# display.net
KiCad netlist of a schematic drawn in Altium Designer
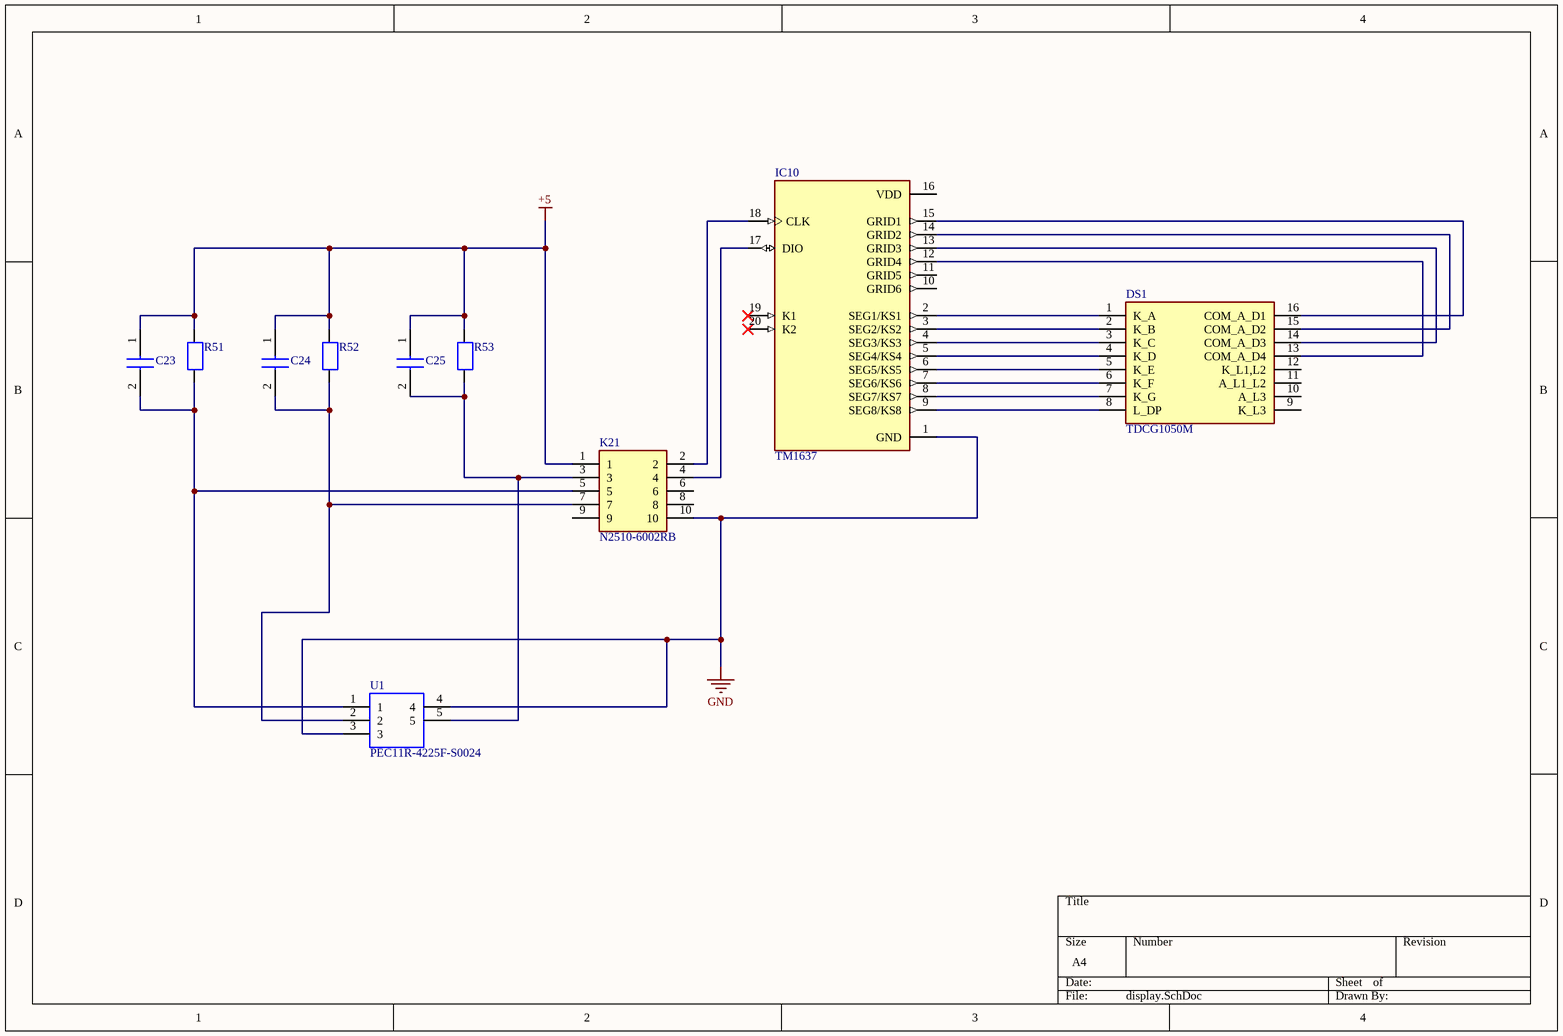
[diagram p0: display.SchDoc]

(export (version "E")
  (design (tool "Eeschema 10.0.6"))
  (components
    (comp (ref "C23")
      (value "08055A130JAT2A")
      (footprint "SamacSys:CAPC2012X94N")
      (description "Capacitor")
      (fields (field (name "MOUSER PART NUMBER") "581-08055A130JAT2A"))
      (libsource (lib "SoldeerboutLib") (part "08055A130JAT2A"))
    )
    (comp (ref "C24")
      (value "08055A130JAT2A")
      (footprint "SamacSys:CAPC2012X94N")
      (description "Capacitor")
      (fields (field (name "MOUSER PART NUMBER") "581-08055A130JAT2A"))
      (libsource (lib "SoldeerboutLib") (part "08055A130JAT2A"))
    )
    (comp (ref "C25")
      (value "08055A130JAT2A")
      (footprint "SamacSys:CAPC2012X94N")
      (description "Capacitor")
      (fields (field (name "MOUSER PART NUMBER") "581-08055A130JAT2A"))
      (libsource (lib "SoldeerboutLib") (part "08055A130JAT2A"))
    )
    (comp (ref "DS1")
      (value "TDCG1050M")
      (footprint "SamacSys:DIPS1016W75P254L4020H725Q16N")
      (description "Display")
      (fields (field (name "MOUSER PART NUMBER") "78-TDCG1050"))
      (libsource (lib "SoldeerboutLib") (part "TDCG1050M"))
    )
    (comp (ref "IC10")
      (value "TM1637")
      (footprint "DIP778W43P254L2612H431Q20N")
      (description "LED Drive Control Special Circuit")
      (fields (field (name "MF") "Titan Micro Electronics"))
      (libsource (lib "SoldeerboutLib") (part "TM1637"))
    )
    (comp (ref "K21")
      (value "N2510-6002RB")
      (footprint "SamacSys:SHDR10W64P254_2X5_2002X859X991P")
      (description "Connector")
      (fields (field (name "MOUSER PART NUMBER") "517-N2510-6002RB"))
      (libsource (lib "SoldeerboutLib") (part "N2510-6002RB"))
    )
    (comp (ref "R51")
      (value "CRCW08050000Z0EA")
      (footprint "RESC2013X50X30LL20T20")
      (fields (field (name "MANUFACTURER") "Vishay Dale"))
      (libsource (lib "SoldeerboutLib") (part "resistor"))
    )
    (comp (ref "R52")
      (value "CRCW08050000Z0EA")
      (footprint "RESC2013X50X30LL20T20")
      (fields (field (name "MANUFACTURER") "Vishay Dale"))
      (libsource (lib "SoldeerboutLib") (part "resistor"))
    )
    (comp (ref "R53")
      (value "CRCW08050000Z0EA")
      (footprint "RESC2013X50X30LL20T20")
      (fields (field (name "MANUFACTURER") "Vishay Dale"))
      (libsource (lib "SoldeerboutLib") (part "resistor"))
    )
    (comp (ref "U1")
      (value "PEC11R-4225F-S0024")
      (footprint "SamacSys:PEC12R-4XXXF-SXXXX_1")
      (description "Undefined or Miscellaneous")
      (fields (field (name "MOUSER PART NUMBER") "652-PEC11R-4225F-S24"))
      (libsource (lib "SoldeerboutLib") (part "PEC11R-4225F-S0024"))
    )
  )
  (nets
    (net (code "1") (name "+5") (class "Default")
      (node (ref "C23") (pin "1") (pinfunction "1_1") (pintype "passive"))
      (node (ref "C24") (pin "1") (pinfunction "1_1") (pintype "passive"))
      (node (ref "C25") (pin "1") (pinfunction "1_1") (pintype "passive"))
      (node (ref "K21") (pin "1") (pinfunction "1_1") (pintype "passive"))
      (node (ref "R51") (pin "1") (pinfunction "1_1") (pintype "passive"))
      (node (ref "R52") (pin "1") (pinfunction "1_1") (pintype "passive"))
      (node (ref "R53") (pin "1") (pinfunction "1_1") (pintype "passive"))
    )
    (net (code "2") (name "GND") (class "Default")
      (node (ref "IC10") (pin "1") (pinfunction "GND_1") (pintype "power_in"))
      (node (ref "K21") (pin "10") (pinfunction "10_10") (pintype "passive"))
      (node (ref "U1") (pin "3") (pinfunction "3_3") (pintype "passive"))
      (node (ref "U1") (pin "4") (pinfunction "4_4") (pintype "passive"))
    )
    (net (code "3") (name "Net-(C23-Pad2)") (class "Default")
      (node (ref "C23") (pin "2") (pinfunction "2_2") (pintype "passive"))
      (node (ref "K21") (pin "5") (pinfunction "5_5") (pintype "passive"))
      (node (ref "R51") (pin "2") (pinfunction "2_2") (pintype "passive"))
      (node (ref "U1") (pin "1") (pinfunction "1_1") (pintype "passive"))
    )
    (net (code "4") (name "Net-(C24-Pad2)") (class "Default")
      (node (ref "C24") (pin "2") (pinfunction "2_2") (pintype "passive"))
      (node (ref "K21") (pin "7") (pinfunction "7_7") (pintype "passive"))
      (node (ref "R52") (pin "2") (pinfunction "2_2") (pintype "passive"))
      (node (ref "U1") (pin "2") (pinfunction "2_2") (pintype "passive"))
    )
    (net (code "5") (name "Net-(C25-Pad2)") (class "Default")
      (node (ref "C25") (pin "2") (pinfunction "2_2") (pintype "passive"))
      (node (ref "K21") (pin "3") (pinfunction "3_3") (pintype "passive"))
      (node (ref "R53") (pin "2") (pinfunction "2_2") (pintype "passive"))
      (node (ref "U1") (pin "5") (pinfunction "5_5") (pintype "passive"))
    )
    (net (code "6") (name "Net-(DS1-COM_A_D1)") (class "Default")
      (node (ref "DS1") (pin "16") (pinfunction "COM_A_D1_16") (pintype "passive"))
      (node (ref "IC10") (pin "15") (pinfunction "GRID1_15") (pintype "output"))
    )
    (net (code "7") (name "Net-(DS1-COM_A_D2)") (class "Default")
      (node (ref "DS1") (pin "15") (pinfunction "COM_A_D2_15") (pintype "passive"))
      (node (ref "IC10") (pin "14") (pinfunction "GRID2_14") (pintype "output"))
    )
    (net (code "8") (name "Net-(DS1-COM_A_D3)") (class "Default")
      (node (ref "DS1") (pin "14") (pinfunction "COM_A_D3_14") (pintype "passive"))
      (node (ref "IC10") (pin "13") (pinfunction "GRID3_13") (pintype "output"))
    )
    (net (code "9") (name "Net-(DS1-COM_A_D4)") (class "Default")
      (node (ref "DS1") (pin "13") (pinfunction "COM_A_D4_13") (pintype "passive"))
      (node (ref "IC10") (pin "12") (pinfunction "GRID4_12") (pintype "output"))
    )
    (net (code "10") (name "Net-(DS1-K_A)") (class "Default")
      (node (ref "DS1") (pin "1") (pinfunction "K_A_1") (pintype "passive"))
      (node (ref "IC10") (pin "2") (pinfunction "SEG1/KS1_2") (pintype "output"))
    )
    (net (code "11") (name "Net-(DS1-K_B)") (class "Default")
      (node (ref "DS1") (pin "2") (pinfunction "K_B_2") (pintype "passive"))
      (node (ref "IC10") (pin "3") (pinfunction "SEG2/KS2_3") (pintype "output"))
    )
    (net (code "12") (name "Net-(DS1-K_C)") (class "Default")
      (node (ref "DS1") (pin "3") (pinfunction "K_C_3") (pintype "passive"))
      (node (ref "IC10") (pin "4") (pinfunction "SEG3/KS3_4") (pintype "output"))
    )
    (net (code "13") (name "Net-(DS1-K_D)") (class "Default")
      (node (ref "DS1") (pin "4") (pinfunction "K_D_4") (pintype "passive"))
      (node (ref "IC10") (pin "5") (pinfunction "SEG4/KS4_5") (pintype "output"))
    )
    (net (code "14") (name "Net-(DS1-K_E)") (class "Default")
      (node (ref "DS1") (pin "5") (pinfunction "K_E_5") (pintype "passive"))
      (node (ref "IC10") (pin "6") (pinfunction "SEG5/KS5_6") (pintype "output"))
    )
    (net (code "15") (name "Net-(DS1-K_F)") (class "Default")
      (node (ref "DS1") (pin "6") (pinfunction "K_F_6") (pintype "passive"))
      (node (ref "IC10") (pin "7") (pinfunction "SEG6/KS6_7") (pintype "output"))
    )
    (net (code "16") (name "Net-(DS1-K_G)") (class "Default")
      (node (ref "DS1") (pin "7") (pinfunction "K_G_7") (pintype "passive"))
      (node (ref "IC10") (pin "8") (pinfunction "SEG7/KS7_8") (pintype "output"))
    )
    (net (code "17") (name "Net-(DS1-L_DP)") (class "Default")
      (node (ref "DS1") (pin "8") (pinfunction "L_DP_8") (pintype "passive"))
      (node (ref "IC10") (pin "9") (pinfunction "SEG8/KS8_9") (pintype "output"))
    )
    (net (code "18") (name "Net-(IC10-CLK)") (class "Default")
      (node (ref "IC10") (pin "18") (pinfunction "CLK_18") (pintype "input"))
      (node (ref "K21") (pin "2") (pinfunction "2_2") (pintype "passive"))
    )
    (net (code "19") (name "Net-(IC10-DIO)") (class "Default")
      (node (ref "IC10") (pin "17") (pinfunction "DIO_17") (pintype "bidirectional"))
      (node (ref "K21") (pin "4") (pinfunction "4_4") (pintype "passive"))
    )
    (net (code "20") (name "unconnected-(DS1-A_L1_L2-Pad11)") (class "Default")
      (node (ref "DS1") (pin "11") (pinfunction "A_L1_L2_11") (pintype "passive"))
    )
    (net (code "21") (name "unconnected-(DS1-A_L3-Pad10)") (class "Default")
      (node (ref "DS1") (pin "10") (pinfunction "A_L3_10") (pintype "passive"))
    )
    (net (code "22") (name "unconnected-(DS1-K_L1,L2-Pad12)") (class "Default")
      (node (ref "DS1") (pin "12") (pinfunction "K_L1,L2_12") (pintype "passive"))
    )
    (net (code "23") (name "unconnected-(DS1-K_L3-Pad9)") (class "Default")
      (node (ref "DS1") (pin "9") (pinfunction "K_L3_9") (pintype "passive"))
    )
    (net (code "24") (name "unconnected-(IC10-GRID5-Pad11)") (class "Default")
      (node (ref "IC10") (pin "11") (pinfunction "GRID5_11") (pintype "output"))
    )
    (net (code "25") (name "unconnected-(IC10-GRID6-Pad10)") (class "Default")
      (node (ref "IC10") (pin "10") (pinfunction "GRID6_10") (pintype "output"))
    )
    (net (code "26") (name "unconnected-(IC10-K1-Pad19)") (class "Default")
      (node (ref "IC10") (pin "19") (pinfunction "K1_19") (pintype "input+no_connect"))
    )
    (net (code "27") (name "unconnected-(IC10-K2-Pad20)") (class "Default")
      (node (ref "IC10") (pin "20") (pinfunction "K2_20") (pintype "input+no_connect"))
    )
    (net (code "28") (name "unconnected-(IC10-VDD-Pad16)") (class "Default")
      (node (ref "IC10") (pin "16") (pinfunction "VDD_16") (pintype "power_in"))
    )
    (net (code "29") (name "unconnected-(K21-Pad6)") (class "Default")
      (node (ref "K21") (pin "6") (pinfunction "6_6") (pintype "passive"))
    )
    (net (code "30") (name "unconnected-(K21-Pad8)") (class "Default")
      (node (ref "K21") (pin "8") (pinfunction "8_8") (pintype "passive"))
    )
    (net (code "31") (name "unconnected-(K21-Pad9)") (class "Default")
      (node (ref "K21") (pin "9") (pinfunction "9_9") (pintype "passive"))
    )
  )
)
